# sunclock.net
KiCad netlist of a schematic drawn in EAGLE
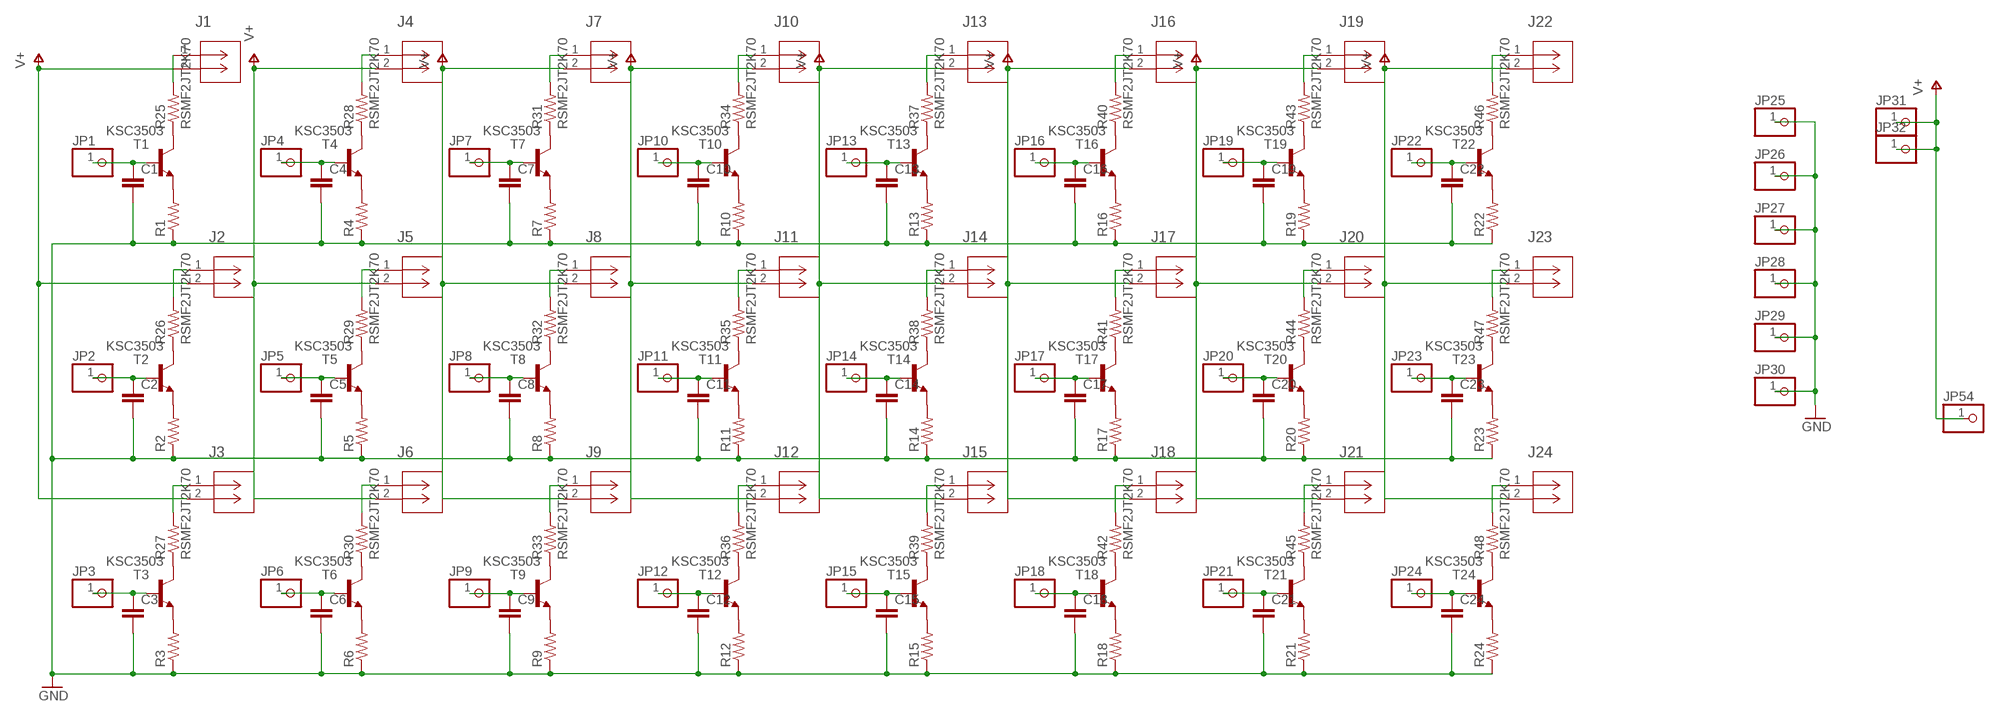
[diagram p0: schematic, sheet 1]

(export (version "E")
  (design (tool "Eeschema 10.0.6"))
  (components
    (comp (ref "C1")
      (value "C-EU050-025X075")
      (footprint "eagle-import:C050-025X075")
      (libsource (lib "eagle-import") (part "C-EU050-025X075"))
    )
    (comp (ref "C2")
      (value "C-EU050-025X075")
      (footprint "eagle-import:C050-025X075")
      (libsource (lib "eagle-import") (part "C-EU050-025X075"))
    )
    (comp (ref "C3")
      (value "C-EU050-025X075")
      (footprint "eagle-import:C050-025X075")
      (libsource (lib "eagle-import") (part "C-EU050-025X075"))
    )
    (comp (ref "C4")
      (value "C-EU050-025X075")
      (footprint "eagle-import:C050-025X075")
      (libsource (lib "eagle-import") (part "C-EU050-025X075"))
    )
    (comp (ref "C5")
      (value "C-EU050-025X075")
      (footprint "eagle-import:C050-025X075")
      (libsource (lib "eagle-import") (part "C-EU050-025X075"))
    )
    (comp (ref "C6")
      (value "C-EU050-025X075")
      (footprint "eagle-import:C050-025X075")
      (libsource (lib "eagle-import") (part "C-EU050-025X075"))
    )
    (comp (ref "C7")
      (value "C-EU050-025X075")
      (footprint "eagle-import:C050-025X075")
      (libsource (lib "eagle-import") (part "C-EU050-025X075"))
    )
    (comp (ref "C8")
      (value "C-EU050-025X075")
      (footprint "eagle-import:C050-025X075")
      (libsource (lib "eagle-import") (part "C-EU050-025X075"))
    )
    (comp (ref "C9")
      (value "C-EU050-025X075")
      (footprint "eagle-import:C050-025X075")
      (libsource (lib "eagle-import") (part "C-EU050-025X075"))
    )
    (comp (ref "C10")
      (value "C-EU050-025X075")
      (footprint "eagle-import:C050-025X075")
      (libsource (lib "eagle-import") (part "C-EU050-025X075"))
    )
    (comp (ref "C11")
      (value "C-EU050-025X075")
      (footprint "eagle-import:C050-025X075")
      (libsource (lib "eagle-import") (part "C-EU050-025X075"))
    )
    (comp (ref "C12")
      (value "C-EU050-025X075")
      (footprint "eagle-import:C050-025X075")
      (libsource (lib "eagle-import") (part "C-EU050-025X075"))
    )
    (comp (ref "C13")
      (value "C-EU050-025X075")
      (footprint "eagle-import:C050-025X075")
      (libsource (lib "eagle-import") (part "C-EU050-025X075"))
    )
    (comp (ref "C14")
      (value "C-EU050-025X075")
      (footprint "eagle-import:C050-025X075")
      (libsource (lib "eagle-import") (part "C-EU050-025X075"))
    )
    (comp (ref "C15")
      (value "C-EU050-025X075")
      (footprint "eagle-import:C050-025X075")
      (libsource (lib "eagle-import") (part "C-EU050-025X075"))
    )
    (comp (ref "C16")
      (value "C-EU050-025X075")
      (footprint "eagle-import:C050-025X075")
      (libsource (lib "eagle-import") (part "C-EU050-025X075"))
    )
    (comp (ref "C17")
      (value "C-EU050-025X075")
      (footprint "eagle-import:C050-025X075")
      (libsource (lib "eagle-import") (part "C-EU050-025X075"))
    )
    (comp (ref "C18")
      (value "C-EU050-025X075")
      (footprint "eagle-import:C050-025X075")
      (libsource (lib "eagle-import") (part "C-EU050-025X075"))
    )
    (comp (ref "C19")
      (value "C-EU050-025X075")
      (footprint "eagle-import:C050-025X075")
      (libsource (lib "eagle-import") (part "C-EU050-025X075"))
    )
    (comp (ref "C20")
      (value "C-EU050-025X075")
      (footprint "eagle-import:C050-025X075")
      (libsource (lib "eagle-import") (part "C-EU050-025X075"))
    )
    (comp (ref "C21")
      (value "C-EU050-025X075")
      (footprint "eagle-import:C050-025X075")
      (libsource (lib "eagle-import") (part "C-EU050-025X075"))
    )
    (comp (ref "C22")
      (value "C-EU050-025X075")
      (footprint "eagle-import:C050-025X075")
      (libsource (lib "eagle-import") (part "C-EU050-025X075"))
    )
    (comp (ref "C23")
      (value "C-EU050-025X075")
      (footprint "eagle-import:C050-025X075")
      (libsource (lib "eagle-import") (part "C-EU050-025X075"))
    )
    (comp (ref "C24")
      (value "C-EU050-025X075")
      (footprint "eagle-import:C050-025X075")
      (libsource (lib "eagle-import") (part "C-EU050-025X075"))
    )
    (comp (ref "J1")
      (value "1776275-2")
      (footprint "eagle-import:CONN2_1776275-2")
      (fields (field (name "COPYRIGHT") "Copyright (C) 2023 Ultra Librarian. All rights reserved."))
      (libsource (lib "eagle-import") (part "1776275-2"))
    )
    (comp (ref "J2")
      (value "1776275-2")
      (footprint "eagle-import:CONN2_1776275-2")
      (fields (field (name "COPYRIGHT") "Copyright (C) 2023 Ultra Librarian. All rights reserved."))
      (libsource (lib "eagle-import") (part "1776275-2"))
    )
    (comp (ref "J3")
      (value "1776275-2")
      (footprint "eagle-import:CONN2_1776275-2")
      (fields (field (name "COPYRIGHT") "Copyright (C) 2023 Ultra Librarian. All rights reserved."))
      (libsource (lib "eagle-import") (part "1776275-2"))
    )
    (comp (ref "J4")
      (value "1776275-2")
      (footprint "eagle-import:CONN2_1776275-2")
      (fields (field (name "COPYRIGHT") "Copyright (C) 2023 Ultra Librarian. All rights reserved."))
      (libsource (lib "eagle-import") (part "1776275-2"))
    )
    (comp (ref "J5")
      (value "1776275-2")
      (footprint "eagle-import:CONN2_1776275-2")
      (fields (field (name "COPYRIGHT") "Copyright (C) 2023 Ultra Librarian. All rights reserved."))
      (libsource (lib "eagle-import") (part "1776275-2"))
    )
    (comp (ref "J6")
      (value "1776275-2")
      (footprint "eagle-import:CONN2_1776275-2")
      (fields (field (name "COPYRIGHT") "Copyright (C) 2023 Ultra Librarian. All rights reserved."))
      (libsource (lib "eagle-import") (part "1776275-2"))
    )
    (comp (ref "J7")
      (value "1776275-2")
      (footprint "eagle-import:CONN2_1776275-2")
      (fields (field (name "COPYRIGHT") "Copyright (C) 2023 Ultra Librarian. All rights reserved."))
      (libsource (lib "eagle-import") (part "1776275-2"))
    )
    (comp (ref "J8")
      (value "1776275-2")
      (footprint "eagle-import:CONN2_1776275-2")
      (fields (field (name "COPYRIGHT") "Copyright (C) 2023 Ultra Librarian. All rights reserved."))
      (libsource (lib "eagle-import") (part "1776275-2"))
    )
    (comp (ref "J9")
      (value "1776275-2")
      (footprint "eagle-import:CONN2_1776275-2")
      (fields (field (name "COPYRIGHT") "Copyright (C) 2023 Ultra Librarian. All rights reserved."))
      (libsource (lib "eagle-import") (part "1776275-2"))
    )
    (comp (ref "J10")
      (value "1776275-2")
      (footprint "eagle-import:CONN2_1776275-2")
      (fields (field (name "COPYRIGHT") "Copyright (C) 2023 Ultra Librarian. All rights reserved."))
      (libsource (lib "eagle-import") (part "1776275-2"))
    )
    (comp (ref "J11")
      (value "1776275-2")
      (footprint "eagle-import:CONN2_1776275-2")
      (fields (field (name "COPYRIGHT") "Copyright (C) 2023 Ultra Librarian. All rights reserved."))
      (libsource (lib "eagle-import") (part "1776275-2"))
    )
    (comp (ref "J12")
      (value "1776275-2")
      (footprint "eagle-import:CONN2_1776275-2")
      (fields (field (name "COPYRIGHT") "Copyright (C) 2023 Ultra Librarian. All rights reserved."))
      (libsource (lib "eagle-import") (part "1776275-2"))
    )
    (comp (ref "J13")
      (value "1776275-2")
      (footprint "eagle-import:CONN2_1776275-2")
      (fields (field (name "COPYRIGHT") "Copyright (C) 2023 Ultra Librarian. All rights reserved."))
      (libsource (lib "eagle-import") (part "1776275-2"))
    )
    (comp (ref "J14")
      (value "1776275-2")
      (footprint "eagle-import:CONN2_1776275-2")
      (fields (field (name "COPYRIGHT") "Copyright (C) 2023 Ultra Librarian. All rights reserved."))
      (libsource (lib "eagle-import") (part "1776275-2"))
    )
    (comp (ref "J15")
      (value "1776275-2")
      (footprint "eagle-import:CONN2_1776275-2")
      (fields (field (name "COPYRIGHT") "Copyright (C) 2023 Ultra Librarian. All rights reserved."))
      (libsource (lib "eagle-import") (part "1776275-2"))
    )
    (comp (ref "J16")
      (value "1776275-2")
      (footprint "eagle-import:CONN2_1776275-2")
      (fields (field (name "COPYRIGHT") "Copyright (C) 2023 Ultra Librarian. All rights reserved."))
      (libsource (lib "eagle-import") (part "1776275-2"))
    )
    (comp (ref "J17")
      (value "1776275-2")
      (footprint "eagle-import:CONN2_1776275-2")
      (fields (field (name "COPYRIGHT") "Copyright (C) 2023 Ultra Librarian. All rights reserved."))
      (libsource (lib "eagle-import") (part "1776275-2"))
    )
    (comp (ref "J18")
      (value "1776275-2")
      (footprint "eagle-import:CONN2_1776275-2")
      (fields (field (name "COPYRIGHT") "Copyright (C) 2023 Ultra Librarian. All rights reserved."))
      (libsource (lib "eagle-import") (part "1776275-2"))
    )
    (comp (ref "J19")
      (value "1776275-2")
      (footprint "eagle-import:CONN2_1776275-2")
      (fields (field (name "COPYRIGHT") "Copyright (C) 2023 Ultra Librarian. All rights reserved."))
      (libsource (lib "eagle-import") (part "1776275-2"))
    )
    (comp (ref "J20")
      (value "1776275-2")
      (footprint "eagle-import:CONN2_1776275-2")
      (fields (field (name "COPYRIGHT") "Copyright (C) 2023 Ultra Librarian. All rights reserved."))
      (libsource (lib "eagle-import") (part "1776275-2"))
    )
    (comp (ref "J21")
      (value "1776275-2")
      (footprint "eagle-import:CONN2_1776275-2")
      (fields (field (name "COPYRIGHT") "Copyright (C) 2023 Ultra Librarian. All rights reserved."))
      (libsource (lib "eagle-import") (part "1776275-2"))
    )
    (comp (ref "J22")
      (value "1776275-2")
      (footprint "eagle-import:CONN2_1776275-2")
      (fields (field (name "COPYRIGHT") "Copyright (C) 2023 Ultra Librarian. All rights reserved."))
      (libsource (lib "eagle-import") (part "1776275-2"))
    )
    (comp (ref "J23")
      (value "1776275-2")
      (footprint "eagle-import:CONN2_1776275-2")
      (fields (field (name "COPYRIGHT") "Copyright (C) 2023 Ultra Librarian. All rights reserved."))
      (libsource (lib "eagle-import") (part "1776275-2"))
    )
    (comp (ref "J24")
      (value "1776275-2")
      (footprint "eagle-import:CONN2_1776275-2")
      (fields (field (name "COPYRIGHT") "Copyright (C) 2023 Ultra Librarian. All rights reserved."))
      (libsource (lib "eagle-import") (part "1776275-2"))
    )
    (comp (ref "JP1")
      (value "PINHD-1X1")
      (footprint "eagle-import:1X01")
      (libsource (lib "eagle-import") (part "PINHD-1X1"))
    )
    (comp (ref "JP2")
      (value "PINHD-1X1")
      (footprint "eagle-import:1X01")
      (libsource (lib "eagle-import") (part "PINHD-1X1"))
    )
    (comp (ref "JP3")
      (value "PINHD-1X1")
      (footprint "eagle-import:1X01")
      (libsource (lib "eagle-import") (part "PINHD-1X1"))
    )
    (comp (ref "JP4")
      (value "PINHD-1X1")
      (footprint "eagle-import:1X01")
      (libsource (lib "eagle-import") (part "PINHD-1X1"))
    )
    (comp (ref "JP5")
      (value "PINHD-1X1")
      (footprint "eagle-import:1X01")
      (libsource (lib "eagle-import") (part "PINHD-1X1"))
    )
    (comp (ref "JP6")
      (value "PINHD-1X1")
      (footprint "eagle-import:1X01")
      (libsource (lib "eagle-import") (part "PINHD-1X1"))
    )
    (comp (ref "JP7")
      (value "PINHD-1X1")
      (footprint "eagle-import:1X01")
      (libsource (lib "eagle-import") (part "PINHD-1X1"))
    )
    (comp (ref "JP8")
      (value "PINHD-1X1")
      (footprint "eagle-import:1X01")
      (libsource (lib "eagle-import") (part "PINHD-1X1"))
    )
    (comp (ref "JP9")
      (value "PINHD-1X1")
      (footprint "eagle-import:1X01")
      (libsource (lib "eagle-import") (part "PINHD-1X1"))
    )
    (comp (ref "JP10")
      (value "PINHD-1X1")
      (footprint "eagle-import:1X01")
      (libsource (lib "eagle-import") (part "PINHD-1X1"))
    )
    (comp (ref "JP11")
      (value "PINHD-1X1")
      (footprint "eagle-import:1X01")
      (libsource (lib "eagle-import") (part "PINHD-1X1"))
    )
    (comp (ref "JP12")
      (value "PINHD-1X1")
      (footprint "eagle-import:1X01")
      (libsource (lib "eagle-import") (part "PINHD-1X1"))
    )
    (comp (ref "JP13")
      (value "PINHD-1X1")
      (footprint "eagle-import:1X01")
      (libsource (lib "eagle-import") (part "PINHD-1X1"))
    )
    (comp (ref "JP14")
      (value "PINHD-1X1")
      (footprint "eagle-import:1X01")
      (libsource (lib "eagle-import") (part "PINHD-1X1"))
    )
    (comp (ref "JP15")
      (value "PINHD-1X1")
      (footprint "eagle-import:1X01")
      (libsource (lib "eagle-import") (part "PINHD-1X1"))
    )
    (comp (ref "JP16")
      (value "PINHD-1X1")
      (footprint "eagle-import:1X01")
      (libsource (lib "eagle-import") (part "PINHD-1X1"))
    )
    (comp (ref "JP17")
      (value "PINHD-1X1")
      (footprint "eagle-import:1X01")
      (libsource (lib "eagle-import") (part "PINHD-1X1"))
    )
    (comp (ref "JP18")
      (value "PINHD-1X1")
      (footprint "eagle-import:1X01")
      (libsource (lib "eagle-import") (part "PINHD-1X1"))
    )
    (comp (ref "JP19")
      (value "PINHD-1X1")
      (footprint "eagle-import:1X01")
      (libsource (lib "eagle-import") (part "PINHD-1X1"))
    )
    (comp (ref "JP20")
      (value "PINHD-1X1")
      (footprint "eagle-import:1X01")
      (libsource (lib "eagle-import") (part "PINHD-1X1"))
    )
    (comp (ref "JP21")
      (value "PINHD-1X1")
      (footprint "eagle-import:1X01")
      (libsource (lib "eagle-import") (part "PINHD-1X1"))
    )
    (comp (ref "JP22")
      (value "PINHD-1X1")
      (footprint "eagle-import:1X01")
      (libsource (lib "eagle-import") (part "PINHD-1X1"))
    )
    (comp (ref "JP23")
      (value "PINHD-1X1")
      (footprint "eagle-import:1X01")
      (libsource (lib "eagle-import") (part "PINHD-1X1"))
    )
    (comp (ref "JP24")
      (value "PINHD-1X1")
      (footprint "eagle-import:1X01")
      (libsource (lib "eagle-import") (part "PINHD-1X1"))
    )
    (comp (ref "JP25")
      (value "PINHD-1X1")
      (footprint "eagle-import:1X01")
      (libsource (lib "eagle-import") (part "PINHD-1X1"))
    )
    (comp (ref "JP26")
      (value "PINHD-1X1")
      (footprint "eagle-import:1X01")
      (libsource (lib "eagle-import") (part "PINHD-1X1"))
    )
    (comp (ref "JP27")
      (value "PINHD-1X1")
      (footprint "eagle-import:1X01")
      (libsource (lib "eagle-import") (part "PINHD-1X1"))
    )
    (comp (ref "JP28")
      (value "PINHD-1X1")
      (footprint "eagle-import:1X01")
      (libsource (lib "eagle-import") (part "PINHD-1X1"))
    )
    (comp (ref "JP29")
      (value "PINHD-1X1")
      (footprint "eagle-import:1X01")
      (libsource (lib "eagle-import") (part "PINHD-1X1"))
    )
    (comp (ref "JP30")
      (value "PINHD-1X1")
      (footprint "eagle-import:1X01")
      (libsource (lib "eagle-import") (part "PINHD-1X1"))
    )
    (comp (ref "JP31")
      (value "PINHD-1X1")
      (footprint "eagle-import:1X01")
      (libsource (lib "eagle-import") (part "PINHD-1X1"))
    )
    (comp (ref "JP32")
      (value "PINHD-1X1")
      (footprint "eagle-import:1X01")
      (libsource (lib "eagle-import") (part "PINHD-1X1"))
    )
    (comp (ref "JP54")
      (value "PINHD-1X1")
      (footprint "eagle-import:1X01")
      (libsource (lib "eagle-import") (part "PINHD-1X1"))
    )
    (comp (ref "R1")
      (value "R-US_0207/10")
      (footprint "eagle-import:0207_10")
      (libsource (lib "eagle-import") (part "R-US_0207/10"))
    )
    (comp (ref "R2")
      (value "R-US_0207/10")
      (footprint "eagle-import:0207_10")
      (libsource (lib "eagle-import") (part "R-US_0207/10"))
    )
    (comp (ref "R3")
      (value "R-US_0207/10")
      (footprint "eagle-import:0207_10")
      (libsource (lib "eagle-import") (part "R-US_0207/10"))
    )
    (comp (ref "R4")
      (value "R-US_0207/10")
      (footprint "eagle-import:0207_10")
      (libsource (lib "eagle-import") (part "R-US_0207/10"))
    )
    (comp (ref "R5")
      (value "R-US_0207/10")
      (footprint "eagle-import:0207_10")
      (libsource (lib "eagle-import") (part "R-US_0207/10"))
    )
    (comp (ref "R6")
      (value "R-US_0207/10")
      (footprint "eagle-import:0207_10")
      (libsource (lib "eagle-import") (part "R-US_0207/10"))
    )
    (comp (ref "R7")
      (value "R-US_0207/10")
      (footprint "eagle-import:0207_10")
      (libsource (lib "eagle-import") (part "R-US_0207/10"))
    )
    (comp (ref "R8")
      (value "R-US_0207/10")
      (footprint "eagle-import:0207_10")
      (libsource (lib "eagle-import") (part "R-US_0207/10"))
    )
    (comp (ref "R9")
      (value "R-US_0207/10")
      (footprint "eagle-import:0207_10")
      (libsource (lib "eagle-import") (part "R-US_0207/10"))
    )
    (comp (ref "R10")
      (value "R-US_0207/10")
      (footprint "eagle-import:0207_10")
      (libsource (lib "eagle-import") (part "R-US_0207/10"))
    )
    (comp (ref "R11")
      (value "R-US_0207/10")
      (footprint "eagle-import:0207_10")
      (libsource (lib "eagle-import") (part "R-US_0207/10"))
    )
    (comp (ref "R12")
      (value "R-US_0207/10")
      (footprint "eagle-import:0207_10")
      (libsource (lib "eagle-import") (part "R-US_0207/10"))
    )
    (comp (ref "R13")
      (value "R-US_0207/10")
      (footprint "eagle-import:0207_10")
      (libsource (lib "eagle-import") (part "R-US_0207/10"))
    )
    (comp (ref "R14")
      (value "R-US_0207/10")
      (footprint "eagle-import:0207_10")
      (libsource (lib "eagle-import") (part "R-US_0207/10"))
    )
    (comp (ref "R15")
      (value "R-US_0207/10")
      (footprint "eagle-import:0207_10")
      (libsource (lib "eagle-import") (part "R-US_0207/10"))
    )
    (comp (ref "R16")
      (value "R-US_0207/10")
      (footprint "eagle-import:0207_10")
      (libsource (lib "eagle-import") (part "R-US_0207/10"))
    )
    (comp (ref "R17")
      (value "R-US_0207/10")
      (footprint "eagle-import:0207_10")
      (libsource (lib "eagle-import") (part "R-US_0207/10"))
    )
    (comp (ref "R18")
      (value "R-US_0207/10")
      (footprint "eagle-import:0207_10")
      (libsource (lib "eagle-import") (part "R-US_0207/10"))
    )
    (comp (ref "R19")
      (value "R-US_0207/10")
      (footprint "eagle-import:0207_10")
      (libsource (lib "eagle-import") (part "R-US_0207/10"))
    )
    (comp (ref "R20")
      (value "R-US_0207/10")
      (footprint "eagle-import:0207_10")
      (libsource (lib "eagle-import") (part "R-US_0207/10"))
    )
    (comp (ref "R21")
      (value "R-US_0207/10")
      (footprint "eagle-import:0207_10")
      (libsource (lib "eagle-import") (part "R-US_0207/10"))
    )
    (comp (ref "R22")
      (value "R-US_0207/10")
      (footprint "eagle-import:0207_10")
      (libsource (lib "eagle-import") (part "R-US_0207/10"))
    )
    (comp (ref "R23")
      (value "R-US_0207/10")
      (footprint "eagle-import:0207_10")
      (libsource (lib "eagle-import") (part "R-US_0207/10"))
    )
    (comp (ref "R24")
      (value "R-US_0207/10")
      (footprint "eagle-import:0207_10")
      (libsource (lib "eagle-import") (part "R-US_0207/10"))
    )
    (comp (ref "R25")
      (value "RSMF2JT2K70")
      (footprint "eagle-import:RESAD1610W80L1100D450B")
      (libsource (lib "eagle-import") (part "RSMF2JT2K70"))
    )
    (comp (ref "R26")
      (value "RSMF2JT2K70")
      (footprint "eagle-import:RESAD1610W80L1100D450B")
      (libsource (lib "eagle-import") (part "RSMF2JT2K70"))
    )
    (comp (ref "R27")
      (value "RSMF2JT2K70")
      (footprint "eagle-import:RESAD1610W80L1100D450B")
      (libsource (lib "eagle-import") (part "RSMF2JT2K70"))
    )
    (comp (ref "R28")
      (value "RSMF2JT2K70")
      (footprint "eagle-import:RESAD1610W80L1100D450B")
      (libsource (lib "eagle-import") (part "RSMF2JT2K70"))
    )
    (comp (ref "R29")
      (value "RSMF2JT2K70")
      (footprint "eagle-import:RESAD1610W80L1100D450B")
      (libsource (lib "eagle-import") (part "RSMF2JT2K70"))
    )
    (comp (ref "R30")
      (value "RSMF2JT2K70")
      (footprint "eagle-import:RESAD1610W80L1100D450B")
      (libsource (lib "eagle-import") (part "RSMF2JT2K70"))
    )
    (comp (ref "R31")
      (value "RSMF2JT2K70")
      (footprint "eagle-import:RESAD1610W80L1100D450B")
      (libsource (lib "eagle-import") (part "RSMF2JT2K70"))
    )
    (comp (ref "R32")
      (value "RSMF2JT2K70")
      (footprint "eagle-import:RESAD1610W80L1100D450B")
      (libsource (lib "eagle-import") (part "RSMF2JT2K70"))
    )
    (comp (ref "R33")
      (value "RSMF2JT2K70")
      (footprint "eagle-import:RESAD1610W80L1100D450B")
      (libsource (lib "eagle-import") (part "RSMF2JT2K70"))
    )
    (comp (ref "R34")
      (value "RSMF2JT2K70")
      (footprint "eagle-import:RESAD1610W80L1100D450B")
      (libsource (lib "eagle-import") (part "RSMF2JT2K70"))
    )
    (comp (ref "R35")
      (value "RSMF2JT2K70")
      (footprint "eagle-import:RESAD1610W80L1100D450B")
      (libsource (lib "eagle-import") (part "RSMF2JT2K70"))
    )
    (comp (ref "R36")
      (value "RSMF2JT2K70")
      (footprint "eagle-import:RESAD1610W80L1100D450B")
      (libsource (lib "eagle-import") (part "RSMF2JT2K70"))
    )
    (comp (ref "R37")
      (value "RSMF2JT2K70")
      (footprint "eagle-import:RESAD1610W80L1100D450B")
      (libsource (lib "eagle-import") (part "RSMF2JT2K70"))
    )
    (comp (ref "R38")
      (value "RSMF2JT2K70")
      (footprint "eagle-import:RESAD1610W80L1100D450B")
      (libsource (lib "eagle-import") (part "RSMF2JT2K70"))
    )
    (comp (ref "R39")
      (value "RSMF2JT2K70")
      (footprint "eagle-import:RESAD1610W80L1100D450B")
      (libsource (lib "eagle-import") (part "RSMF2JT2K70"))
    )
    (comp (ref "R40")
      (value "RSMF2JT2K70")
      (footprint "eagle-import:RESAD1610W80L1100D450B")
      (libsource (lib "eagle-import") (part "RSMF2JT2K70"))
    )
    (comp (ref "R41")
      (value "RSMF2JT2K70")
      (footprint "eagle-import:RESAD1610W80L1100D450B")
      (libsource (lib "eagle-import") (part "RSMF2JT2K70"))
    )
    (comp (ref "R42")
      (value "RSMF2JT2K70")
      (footprint "eagle-import:RESAD1610W80L1100D450B")
      (libsource (lib "eagle-import") (part "RSMF2JT2K70"))
    )
    (comp (ref "R43")
      (value "RSMF2JT2K70")
      (footprint "eagle-import:RESAD1610W80L1100D450B")
      (libsource (lib "eagle-import") (part "RSMF2JT2K70"))
    )
    (comp (ref "R44")
      (value "RSMF2JT2K70")
      (footprint "eagle-import:RESAD1610W80L1100D450B")
      (libsource (lib "eagle-import") (part "RSMF2JT2K70"))
    )
    (comp (ref "R45")
      (value "RSMF2JT2K70")
      (footprint "eagle-import:RESAD1610W80L1100D450B")
      (libsource (lib "eagle-import") (part "RSMF2JT2K70"))
    )
    (comp (ref "R46")
      (value "RSMF2JT2K70")
      (footprint "eagle-import:RESAD1610W80L1100D450B")
      (libsource (lib "eagle-import") (part "RSMF2JT2K70"))
    )
    (comp (ref "R47")
      (value "RSMF2JT2K70")
      (footprint "eagle-import:RESAD1610W80L1100D450B")
      (libsource (lib "eagle-import") (part "RSMF2JT2K70"))
    )
    (comp (ref "R48")
      (value "RSMF2JT2K70")
      (footprint "eagle-import:RESAD1610W80L1100D450B")
      (libsource (lib "eagle-import") (part "RSMF2JT2K70"))
    )
    (comp (ref "T1")
      (value "KSC3503")
      (footprint "eagle-import:TO126V_")
      (libsource (lib "eagle-import") (part "KSC3503"))
    )
    (comp (ref "T2")
      (value "KSC3503")
      (footprint "eagle-import:TO126V_")
      (libsource (lib "eagle-import") (part "KSC3503"))
    )
    (comp (ref "T3")
      (value "KSC3503")
      (footprint "eagle-import:TO126V_")
      (libsource (lib "eagle-import") (part "KSC3503"))
    )
    (comp (ref "T4")
      (value "KSC3503")
      (footprint "eagle-import:TO126V_")
      (libsource (lib "eagle-import") (part "KSC3503"))
    )
    (comp (ref "T5")
      (value "KSC3503")
      (footprint "eagle-import:TO126V_")
      (libsource (lib "eagle-import") (part "KSC3503"))
    )
    (comp (ref "T6")
      (value "KSC3503")
      (footprint "eagle-import:TO126V_")
      (libsource (lib "eagle-import") (part "KSC3503"))
    )
    (comp (ref "T7")
      (value "KSC3503")
      (footprint "eagle-import:TO126V_")
      (libsource (lib "eagle-import") (part "KSC3503"))
    )
    (comp (ref "T8")
      (value "KSC3503")
      (footprint "eagle-import:TO126V_")
      (libsource (lib "eagle-import") (part "KSC3503"))
    )
    (comp (ref "T9")
      (value "KSC3503")
      (footprint "eagle-import:TO126V_")
      (libsource (lib "eagle-import") (part "KSC3503"))
    )
    (comp (ref "T10")
      (value "KSC3503")
      (footprint "eagle-import:TO126V_")
      (libsource (lib "eagle-import") (part "KSC3503"))
    )
    (comp (ref "T11")
      (value "KSC3503")
      (footprint "eagle-import:TO126V_")
      (libsource (lib "eagle-import") (part "KSC3503"))
    )
    (comp (ref "T12")
      (value "KSC3503")
      (footprint "eagle-import:TO126V_")
      (libsource (lib "eagle-import") (part "KSC3503"))
    )
    (comp (ref "T13")
      (value "KSC3503")
      (footprint "eagle-import:TO126V_")
      (libsource (lib "eagle-import") (part "KSC3503"))
    )
    (comp (ref "T14")
      (value "KSC3503")
      (footprint "eagle-import:TO126V_")
      (libsource (lib "eagle-import") (part "KSC3503"))
    )
    (comp (ref "T15")
      (value "KSC3503")
      (footprint "eagle-import:TO126V_")
      (libsource (lib "eagle-import") (part "KSC3503"))
    )
    (comp (ref "T16")
      (value "KSC3503")
      (footprint "eagle-import:TO126V_")
      (libsource (lib "eagle-import") (part "KSC3503"))
    )
    (comp (ref "T17")
      (value "KSC3503")
      (footprint "eagle-import:TO126V_")
      (libsource (lib "eagle-import") (part "KSC3503"))
    )
    (comp (ref "T18")
      (value "KSC3503")
      (footprint "eagle-import:TO126V_")
      (libsource (lib "eagle-import") (part "KSC3503"))
    )
    (comp (ref "T19")
      (value "KSC3503")
      (footprint "eagle-import:TO126V_")
      (libsource (lib "eagle-import") (part "KSC3503"))
    )
    (comp (ref "T20")
      (value "KSC3503")
      (footprint "eagle-import:TO126V_")
      (libsource (lib "eagle-import") (part "KSC3503"))
    )
    (comp (ref "T21")
      (value "KSC3503")
      (footprint "eagle-import:TO126V_")
      (libsource (lib "eagle-import") (part "KSC3503"))
    )
    (comp (ref "T22")
      (value "KSC3503")
      (footprint "eagle-import:TO126V_")
      (libsource (lib "eagle-import") (part "KSC3503"))
    )
    (comp (ref "T23")
      (value "KSC3503")
      (footprint "eagle-import:TO126V_")
      (libsource (lib "eagle-import") (part "KSC3503"))
    )
    (comp (ref "T24")
      (value "KSC3503")
      (footprint "eagle-import:TO126V_")
      (libsource (lib "eagle-import") (part "KSC3503"))
    )
  )
  (nets
    (net (code "1") (name "GND") (class "Default")
      (node (ref "C1") (pin "2") (pinfunction "2_2") (pintype "passive"))
      (node (ref "C10") (pin "2") (pinfunction "2_2") (pintype "passive"))
      (node (ref "C11") (pin "2") (pinfunction "2_2") (pintype "passive"))
      (node (ref "C12") (pin "2") (pinfunction "2_2") (pintype "passive"))
      (node (ref "C13") (pin "2") (pinfunction "2_2") (pintype "passive"))
      (node (ref "C14") (pin "2") (pinfunction "2_2") (pintype "passive"))
      (node (ref "C15") (pin "2") (pinfunction "2_2") (pintype "passive"))
      (node (ref "C16") (pin "2") (pinfunction "2_2") (pintype "passive"))
      (node (ref "C17") (pin "2") (pinfunction "2_2") (pintype "passive"))
      (node (ref "C18") (pin "2") (pinfunction "2_2") (pintype "passive"))
      (node (ref "C19") (pin "2") (pinfunction "2_2") (pintype "passive"))
      (node (ref "C2") (pin "2") (pinfunction "2_2") (pintype "passive"))
      (node (ref "C20") (pin "2") (pinfunction "2_2") (pintype "passive"))
      (node (ref "C21") (pin "2") (pinfunction "2_2") (pintype "passive"))
      (node (ref "C22") (pin "2") (pinfunction "2_2") (pintype "passive"))
      (node (ref "C23") (pin "2") (pinfunction "2_2") (pintype "passive"))
      (node (ref "C24") (pin "2") (pinfunction "2_2") (pintype "passive"))
      (node (ref "C3") (pin "2") (pinfunction "2_2") (pintype "passive"))
      (node (ref "C4") (pin "2") (pinfunction "2_2") (pintype "passive"))
      (node (ref "C5") (pin "2") (pinfunction "2_2") (pintype "passive"))
      (node (ref "C6") (pin "2") (pinfunction "2_2") (pintype "passive"))
      (node (ref "C7") (pin "2") (pinfunction "2_2") (pintype "passive"))
      (node (ref "C8") (pin "2") (pinfunction "2_2") (pintype "passive"))
      (node (ref "C9") (pin "2") (pinfunction "2_2") (pintype "passive"))
      (node (ref "JP25") (pin "1") (pinfunction "1_1") (pintype "passive"))
      (node (ref "JP26") (pin "1") (pinfunction "1_1") (pintype "passive"))
      (node (ref "JP27") (pin "1") (pinfunction "1_1") (pintype "passive"))
      (node (ref "JP28") (pin "1") (pinfunction "1_1") (pintype "passive"))
      (node (ref "JP29") (pin "1") (pinfunction "1_1") (pintype "passive"))
      (node (ref "JP30") (pin "1") (pinfunction "1_1") (pintype "passive"))
      (node (ref "R1") (pin "1") (pinfunction "1_1") (pintype "passive"))
      (node (ref "R10") (pin "1") (pinfunction "1_1") (pintype "passive"))
      (node (ref "R11") (pin "1") (pinfunction "1_1") (pintype "passive"))
      (node (ref "R12") (pin "1") (pinfunction "1_1") (pintype "passive"))
      (node (ref "R13") (pin "1") (pinfunction "1_1") (pintype "passive"))
      (node (ref "R14") (pin "1") (pinfunction "1_1") (pintype "passive"))
      (node (ref "R15") (pin "1") (pinfunction "1_1") (pintype "passive"))
      (node (ref "R16") (pin "1") (pinfunction "1_1") (pintype "passive"))
      (node (ref "R17") (pin "1") (pinfunction "1_1") (pintype "passive"))
      (node (ref "R18") (pin "1") (pinfunction "1_1") (pintype "passive"))
      (node (ref "R19") (pin "1") (pinfunction "1_1") (pintype "passive"))
      (node (ref "R2") (pin "1") (pinfunction "1_1") (pintype "passive"))
      (node (ref "R20") (pin "1") (pinfunction "1_1") (pintype "passive"))
      (node (ref "R21") (pin "1") (pinfunction "1_1") (pintype "passive"))
      (node (ref "R22") (pin "1") (pinfunction "1_1") (pintype "passive"))
      (node (ref "R23") (pin "1") (pinfunction "1_1") (pintype "passive"))
      (node (ref "R24") (pin "1") (pinfunction "1_1") (pintype "passive"))
      (node (ref "R3") (pin "1") (pinfunction "1_1") (pintype "passive"))
      (node (ref "R4") (pin "1") (pinfunction "1_1") (pintype "passive"))
      (node (ref "R5") (pin "1") (pinfunction "1_1") (pintype "passive"))
      (node (ref "R6") (pin "1") (pinfunction "1_1") (pintype "passive"))
      (node (ref "R7") (pin "1") (pinfunction "1_1") (pintype "passive"))
      (node (ref "R8") (pin "1") (pinfunction "1_1") (pintype "passive"))
      (node (ref "R9") (pin "1") (pinfunction "1_1") (pintype "passive"))
    )
    (net (code "2") (name "Net-(J1-Pad1)") (class "Default")
      (node (ref "J1") (pin "1") (pinfunction "1_1") (pintype "passive"))
      (node (ref "R25") (pin "2") (pinfunction "2_2") (pintype "passive"))
    )
    (net (code "3") (name "Net-(J2-Pad1)") (class "Default")
      (node (ref "J2") (pin "1") (pinfunction "1_1") (pintype "passive"))
      (node (ref "R26") (pin "2") (pinfunction "2_2") (pintype "passive"))
    )
    (net (code "4") (name "Net-(J3-Pad1)") (class "Default")
      (node (ref "J3") (pin "1") (pinfunction "1_1") (pintype "passive"))
      (node (ref "R27") (pin "2") (pinfunction "2_2") (pintype "passive"))
    )
    (net (code "5") (name "Net-(J4-Pad1)") (class "Default")
      (node (ref "J4") (pin "1") (pinfunction "1_1") (pintype "passive"))
      (node (ref "R28") (pin "2") (pinfunction "2_2") (pintype "passive"))
    )
    (net (code "6") (name "Net-(J5-Pad1)") (class "Default")
      (node (ref "J5") (pin "1") (pinfunction "1_1") (pintype "passive"))
      (node (ref "R29") (pin "2") (pinfunction "2_2") (pintype "passive"))
    )
    (net (code "7") (name "Net-(J6-Pad1)") (class "Default")
      (node (ref "J6") (pin "1") (pinfunction "1_1") (pintype "passive"))
      (node (ref "R30") (pin "2") (pinfunction "2_2") (pintype "passive"))
    )
    (net (code "8") (name "Net-(J7-Pad1)") (class "Default")
      (node (ref "J7") (pin "1") (pinfunction "1_1") (pintype "passive"))
      (node (ref "R31") (pin "2") (pinfunction "2_2") (pintype "passive"))
    )
    (net (code "9") (name "Net-(J8-Pad1)") (class "Default")
      (node (ref "J8") (pin "1") (pinfunction "1_1") (pintype "passive"))
      (node (ref "R32") (pin "2") (pinfunction "2_2") (pintype "passive"))
    )
    (net (code "10") (name "Net-(J9-Pad1)") (class "Default")
      (node (ref "J9") (pin "1") (pinfunction "1_1") (pintype "passive"))
      (node (ref "R33") (pin "2") (pinfunction "2_2") (pintype "passive"))
    )
    (net (code "11") (name "Net-(J10-Pad1)") (class "Default")
      (node (ref "J10") (pin "1") (pinfunction "1_1") (pintype "passive"))
      (node (ref "R34") (pin "2") (pinfunction "2_2") (pintype "passive"))
    )
    (net (code "12") (name "Net-(J11-Pad1)") (class "Default")
      (node (ref "J11") (pin "1") (pinfunction "1_1") (pintype "passive"))
      (node (ref "R35") (pin "2") (pinfunction "2_2") (pintype "passive"))
    )
    (net (code "13") (name "Net-(J12-Pad1)") (class "Default")
      (node (ref "J12") (pin "1") (pinfunction "1_1") (pintype "passive"))
      (node (ref "R36") (pin "2") (pinfunction "2_2") (pintype "passive"))
    )
    (net (code "14") (name "Net-(J13-Pad1)") (class "Default")
      (node (ref "J13") (pin "1") (pinfunction "1_1") (pintype "passive"))
      (node (ref "R37") (pin "2") (pinfunction "2_2") (pintype "passive"))
    )
    (net (code "15") (name "Net-(J14-Pad1)") (class "Default")
      (node (ref "J14") (pin "1") (pinfunction "1_1") (pintype "passive"))
      (node (ref "R38") (pin "2") (pinfunction "2_2") (pintype "passive"))
    )
    (net (code "16") (name "Net-(J15-Pad1)") (class "Default")
      (node (ref "J15") (pin "1") (pinfunction "1_1") (pintype "passive"))
      (node (ref "R39") (pin "2") (pinfunction "2_2") (pintype "passive"))
    )
    (net (code "17") (name "Net-(J16-Pad1)") (class "Default")
      (node (ref "J16") (pin "1") (pinfunction "1_1") (pintype "passive"))
      (node (ref "R40") (pin "2") (pinfunction "2_2") (pintype "passive"))
    )
    (net (code "18") (name "Net-(J17-Pad1)") (class "Default")
      (node (ref "J17") (pin "1") (pinfunction "1_1") (pintype "passive"))
      (node (ref "R41") (pin "2") (pinfunction "2_2") (pintype "passive"))
    )
    (net (code "19") (name "Net-(J18-Pad1)") (class "Default")
      (node (ref "J18") (pin "1") (pinfunction "1_1") (pintype "passive"))
      (node (ref "R42") (pin "2") (pinfunction "2_2") (pintype "passive"))
    )
    (net (code "20") (name "Net-(J19-Pad1)") (class "Default")
      (node (ref "J19") (pin "1") (pinfunction "1_1") (pintype "passive"))
      (node (ref "R43") (pin "2") (pinfunction "2_2") (pintype "passive"))
    )
    (net (code "21") (name "Net-(J20-Pad1)") (class "Default")
      (node (ref "J20") (pin "1") (pinfunction "1_1") (pintype "passive"))
      (node (ref "R44") (pin "2") (pinfunction "2_2") (pintype "passive"))
    )
    (net (code "22") (name "Net-(J21-Pad1)") (class "Default")
      (node (ref "J21") (pin "1") (pinfunction "1_1") (pintype "passive"))
      (node (ref "R45") (pin "2") (pinfunction "2_2") (pintype "passive"))
    )
    (net (code "23") (name "Net-(J22-Pad1)") (class "Default")
      (node (ref "J22") (pin "1") (pinfunction "1_1") (pintype "passive"))
      (node (ref "R46") (pin "2") (pinfunction "2_2") (pintype "passive"))
    )
    (net (code "24") (name "Net-(J23-Pad1)") (class "Default")
      (node (ref "J23") (pin "1") (pinfunction "1_1") (pintype "passive"))
      (node (ref "R47") (pin "2") (pinfunction "2_2") (pintype "passive"))
    )
    (net (code "25") (name "Net-(J24-Pad1)") (class "Default")
      (node (ref "J24") (pin "1") (pinfunction "1_1") (pintype "passive"))
      (node (ref "R48") (pin "2") (pinfunction "2_2") (pintype "passive"))
    )
    (net (code "26") (name "Net-(T1-B)") (class "Default")
      (node (ref "C1") (pin "1") (pinfunction "1_1") (pintype "passive"))
      (node (ref "JP1") (pin "1") (pinfunction "1_1") (pintype "passive"))
      (node (ref "T1") (pin "3") (pinfunction "B_3") (pintype "passive"))
    )
    (net (code "27") (name "Net-(T1-C)") (class "Default")
      (node (ref "R25") (pin "1") (pinfunction "1_1") (pintype "passive"))
      (node (ref "T1") (pin "2") (pinfunction "C_2") (pintype "passive"))
    )
    (net (code "28") (name "Net-(T1-E)") (class "Default")
      (node (ref "R1") (pin "2") (pinfunction "2_2") (pintype "passive"))
      (node (ref "T1") (pin "1") (pinfunction "E_1") (pintype "passive"))
    )
    (net (code "29") (name "Net-(T2-B)") (class "Default")
      (node (ref "C2") (pin "1") (pinfunction "1_1") (pintype "passive"))
      (node (ref "JP2") (pin "1") (pinfunction "1_1") (pintype "passive"))
      (node (ref "T2") (pin "3") (pinfunction "B_3") (pintype "passive"))
    )
    (net (code "30") (name "Net-(T2-C)") (class "Default")
      (node (ref "R26") (pin "1") (pinfunction "1_1") (pintype "passive"))
      (node (ref "T2") (pin "2") (pinfunction "C_2") (pintype "passive"))
    )
    (net (code "31") (name "Net-(T2-E)") (class "Default")
      (node (ref "R2") (pin "2") (pinfunction "2_2") (pintype "passive"))
      (node (ref "T2") (pin "1") (pinfunction "E_1") (pintype "passive"))
    )
    (net (code "32") (name "Net-(T3-B)") (class "Default")
      (node (ref "C3") (pin "1") (pinfunction "1_1") (pintype "passive"))
      (node (ref "JP3") (pin "1") (pinfunction "1_1") (pintype "passive"))
      (node (ref "T3") (pin "3") (pinfunction "B_3") (pintype "passive"))
    )
    (net (code "33") (name "Net-(T3-C)") (class "Default")
      (node (ref "R27") (pin "1") (pinfunction "1_1") (pintype "passive"))
      (node (ref "T3") (pin "2") (pinfunction "C_2") (pintype "passive"))
    )
    (net (code "34") (name "Net-(T3-E)") (class "Default")
      (node (ref "R3") (pin "2") (pinfunction "2_2") (pintype "passive"))
      (node (ref "T3") (pin "1") (pinfunction "E_1") (pintype "passive"))
    )
    (net (code "35") (name "Net-(T4-B)") (class "Default")
      (node (ref "C4") (pin "1") (pinfunction "1_1") (pintype "passive"))
      (node (ref "JP4") (pin "1") (pinfunction "1_1") (pintype "passive"))
      (node (ref "T4") (pin "3") (pinfunction "B_3") (pintype "passive"))
    )
    (net (code "36") (name "Net-(T4-C)") (class "Default")
      (node (ref "R28") (pin "1") (pinfunction "1_1") (pintype "passive"))
      (node (ref "T4") (pin "2") (pinfunction "C_2") (pintype "passive"))
    )
    (net (code "37") (name "Net-(T4-E)") (class "Default")
      (node (ref "R4") (pin "2") (pinfunction "2_2") (pintype "passive"))
      (node (ref "T4") (pin "1") (pinfunction "E_1") (pintype "passive"))
    )
    (net (code "38") (name "Net-(T5-B)") (class "Default")
      (node (ref "C5") (pin "1") (pinfunction "1_1") (pintype "passive"))
      (node (ref "JP5") (pin "1") (pinfunction "1_1") (pintype "passive"))
      (node (ref "T5") (pin "3") (pinfunction "B_3") (pintype "passive"))
    )
    (net (code "39") (name "Net-(T5-C)") (class "Default")
      (node (ref "R29") (pin "1") (pinfunction "1_1") (pintype "passive"))
      (node (ref "T5") (pin "2") (pinfunction "C_2") (pintype "passive"))
    )
    (net (code "40") (name "Net-(T5-E)") (class "Default")
      (node (ref "R5") (pin "2") (pinfunction "2_2") (pintype "passive"))
      (node (ref "T5") (pin "1") (pinfunction "E_1") (pintype "passive"))
    )
    (net (code "41") (name "Net-(T6-B)") (class "Default")
      (node (ref "C6") (pin "1") (pinfunction "1_1") (pintype "passive"))
      (node (ref "JP6") (pin "1") (pinfunction "1_1") (pintype "passive"))
      (node (ref "T6") (pin "3") (pinfunction "B_3") (pintype "passive"))
    )
    (net (code "42") (name "Net-(T6-C)") (class "Default")
      (node (ref "R30") (pin "1") (pinfunction "1_1") (pintype "passive"))
      (node (ref "T6") (pin "2") (pinfunction "C_2") (pintype "passive"))
    )
    (net (code "43") (name "Net-(T6-E)") (class "Default")
      (node (ref "R6") (pin "2") (pinfunction "2_2") (pintype "passive"))
      (node (ref "T6") (pin "1") (pinfunction "E_1") (pintype "passive"))
    )
    (net (code "44") (name "Net-(T7-B)") (class "Default")
      (node (ref "C7") (pin "1") (pinfunction "1_1") (pintype "passive"))
      (node (ref "JP7") (pin "1") (pinfunction "1_1") (pintype "passive"))
      (node (ref "T7") (pin "3") (pinfunction "B_3") (pintype "passive"))
    )
    (net (code "45") (name "Net-(T7-C)") (class "Default")
      (node (ref "R31") (pin "1") (pinfunction "1_1") (pintype "passive"))
      (node (ref "T7") (pin "2") (pinfunction "C_2") (pintype "passive"))
    )
    (net (code "46") (name "Net-(T7-E)") (class "Default")
      (node (ref "R7") (pin "2") (pinfunction "2_2") (pintype "passive"))
      (node (ref "T7") (pin "1") (pinfunction "E_1") (pintype "passive"))
    )
    (net (code "47") (name "Net-(T8-B)") (class "Default")
      (node (ref "C8") (pin "1") (pinfunction "1_1") (pintype "passive"))
      (node (ref "JP8") (pin "1") (pinfunction "1_1") (pintype "passive"))
      (node (ref "T8") (pin "3") (pinfunction "B_3") (pintype "passive"))
    )
    (net (code "48") (name "Net-(T8-C)") (class "Default")
      (node (ref "R32") (pin "1") (pinfunction "1_1") (pintype "passive"))
      (node (ref "T8") (pin "2") (pinfunction "C_2") (pintype "passive"))
    )
    (net (code "49") (name "Net-(T8-E)") (class "Default")
      (node (ref "R8") (pin "2") (pinfunction "2_2") (pintype "passive"))
      (node (ref "T8") (pin "1") (pinfunction "E_1") (pintype "passive"))
    )
    (net (code "50") (name "Net-(T9-B)") (class "Default")
      (node (ref "C9") (pin "1") (pinfunction "1_1") (pintype "passive"))
      (node (ref "JP9") (pin "1") (pinfunction "1_1") (pintype "passive"))
      (node (ref "T9") (pin "3") (pinfunction "B_3") (pintype "passive"))
    )
    (net (code "51") (name "Net-(T9-C)") (class "Default")
      (node (ref "R33") (pin "1") (pinfunction "1_1") (pintype "passive"))
      (node (ref "T9") (pin "2") (pinfunction "C_2") (pintype "passive"))
    )
    (net (code "52") (name "Net-(T9-E)") (class "Default")
      (node (ref "R9") (pin "2") (pinfunction "2_2") (pintype "passive"))
      (node (ref "T9") (pin "1") (pinfunction "E_1") (pintype "passive"))
    )
    (net (code "53") (name "Net-(T10-B)") (class "Default")
      (node (ref "C10") (pin "1") (pinfunction "1_1") (pintype "passive"))
      (node (ref "JP10") (pin "1") (pinfunction "1_1") (pintype "passive"))
      (node (ref "T10") (pin "3") (pinfunction "B_3") (pintype "passive"))
    )
    (net (code "54") (name "Net-(T10-C)") (class "Default")
      (node (ref "R34") (pin "1") (pinfunction "1_1") (pintype "passive"))
      (node (ref "T10") (pin "2") (pinfunction "C_2") (pintype "passive"))
    )
    (net (code "55") (name "Net-(T10-E)") (class "Default")
      (node (ref "R10") (pin "2") (pinfunction "2_2") (pintype "passive"))
      (node (ref "T10") (pin "1") (pinfunction "E_1") (pintype "passive"))
    )
    (net (code "56") (name "Net-(T11-B)") (class "Default")
      (node (ref "C11") (pin "1") (pinfunction "1_1") (pintype "passive"))
      (node (ref "JP11") (pin "1") (pinfunction "1_1") (pintype "passive"))
      (node (ref "T11") (pin "3") (pinfunction "B_3") (pintype "passive"))
    )
    (net (code "57") (name "Net-(T11-C)") (class "Default")
      (node (ref "R35") (pin "1") (pinfunction "1_1") (pintype "passive"))
      (node (ref "T11") (pin "2") (pinfunction "C_2") (pintype "passive"))
    )
    (net (code "58") (name "Net-(T11-E)") (class "Default")
      (node (ref "R11") (pin "2") (pinfunction "2_2") (pintype "passive"))
      (node (ref "T11") (pin "1") (pinfunction "E_1") (pintype "passive"))
    )
    (net (code "59") (name "Net-(T12-B)") (class "Default")
      (node (ref "C12") (pin "1") (pinfunction "1_1") (pintype "passive"))
      (node (ref "JP12") (pin "1") (pinfunction "1_1") (pintype "passive"))
      (node (ref "T12") (pin "3") (pinfunction "B_3") (pintype "passive"))
    )
    (net (code "60") (name "Net-(T12-C)") (class "Default")
      (node (ref "R36") (pin "1") (pinfunction "1_1") (pintype "passive"))
      (node (ref "T12") (pin "2") (pinfunction "C_2") (pintype "passive"))
    )
    (net (code "61") (name "Net-(T12-E)") (class "Default")
      (node (ref "R12") (pin "2") (pinfunction "2_2") (pintype "passive"))
      (node (ref "T12") (pin "1") (pinfunction "E_1") (pintype "passive"))
    )
    (net (code "62") (name "Net-(T13-B)") (class "Default")
      (node (ref "C13") (pin "1") (pinfunction "1_1") (pintype "passive"))
      (node (ref "JP13") (pin "1") (pinfunction "1_1") (pintype "passive"))
      (node (ref "T13") (pin "3") (pinfunction "B_3") (pintype "passive"))
    )
    (net (code "63") (name "Net-(T13-C)") (class "Default")
      (node (ref "R37") (pin "1") (pinfunction "1_1") (pintype "passive"))
      (node (ref "T13") (pin "2") (pinfunction "C_2") (pintype "passive"))
    )
    (net (code "64") (name "Net-(T13-E)") (class "Default")
      (node (ref "R13") (pin "2") (pinfunction "2_2") (pintype "passive"))
      (node (ref "T13") (pin "1") (pinfunction "E_1") (pintype "passive"))
    )
    (net (code "65") (name "Net-(T14-B)") (class "Default")
      (node (ref "C14") (pin "1") (pinfunction "1_1") (pintype "passive"))
      (node (ref "JP14") (pin "1") (pinfunction "1_1") (pintype "passive"))
      (node (ref "T14") (pin "3") (pinfunction "B_3") (pintype "passive"))
    )
    (net (code "66") (name "Net-(T14-C)") (class "Default")
      (node (ref "R38") (pin "1") (pinfunction "1_1") (pintype "passive"))
      (node (ref "T14") (pin "2") (pinfunction "C_2") (pintype "passive"))
    )
    (net (code "67") (name "Net-(T14-E)") (class "Default")
      (node (ref "R14") (pin "2") (pinfunction "2_2") (pintype "passive"))
      (node (ref "T14") (pin "1") (pinfunction "E_1") (pintype "passive"))
    )
    (net (code "68") (name "Net-(T15-B)") (class "Default")
      (node (ref "C15") (pin "1") (pinfunction "1_1") (pintype "passive"))
      (node (ref "JP15") (pin "1") (pinfunction "1_1") (pintype "passive"))
      (node (ref "T15") (pin "3") (pinfunction "B_3") (pintype "passive"))
    )
    (net (code "69") (name "Net-(T15-C)") (class "Default")
      (node (ref "R39") (pin "1") (pinfunction "1_1") (pintype "passive"))
      (node (ref "T15") (pin "2") (pinfunction "C_2") (pintype "passive"))
    )
    (net (code "70") (name "Net-(T15-E)") (class "Default")
      (node (ref "R15") (pin "2") (pinfunction "2_2") (pintype "passive"))
      (node (ref "T15") (pin "1") (pinfunction "E_1") (pintype "passive"))
    )
    (net (code "71") (name "Net-(T16-B)") (class "Default")
      (node (ref "C16") (pin "1") (pinfunction "1_1") (pintype "passive"))
      (node (ref "JP16") (pin "1") (pinfunction "1_1") (pintype "passive"))
      (node (ref "T16") (pin "3") (pinfunction "B_3") (pintype "passive"))
    )
    (net (code "72") (name "Net-(T16-C)") (class "Default")
      (node (ref "R40") (pin "1") (pinfunction "1_1") (pintype "passive"))
      (node (ref "T16") (pin "2") (pinfunction "C_2") (pintype "passive"))
    )
    (net (code "73") (name "Net-(T16-E)") (class "Default")
      (node (ref "R16") (pin "2") (pinfunction "2_2") (pintype "passive"))
      (node (ref "T16") (pin "1") (pinfunction "E_1") (pintype "passive"))
    )
    (net (code "74") (name "Net-(T17-B)") (class "Default")
      (node (ref "C17") (pin "1") (pinfunction "1_1") (pintype "passive"))
      (node (ref "JP17") (pin "1") (pinfunction "1_1") (pintype "passive"))
      (node (ref "T17") (pin "3") (pinfunction "B_3") (pintype "passive"))
    )
    (net (code "75") (name "Net-(T17-C)") (class "Default")
      (node (ref "R41") (pin "1") (pinfunction "1_1") (pintype "passive"))
      (node (ref "T17") (pin "2") (pinfunction "C_2") (pintype "passive"))
    )
    (net (code "76") (name "Net-(T17-E)") (class "Default")
      (node (ref "R17") (pin "2") (pinfunction "2_2") (pintype "passive"))
      (node (ref "T17") (pin "1") (pinfunction "E_1") (pintype "passive"))
    )
    (net (code "77") (name "Net-(T18-B)") (class "Default")
      (node (ref "C18") (pin "1") (pinfunction "1_1") (pintype "passive"))
      (node (ref "JP18") (pin "1") (pinfunction "1_1") (pintype "passive"))
      (node (ref "T18") (pin "3") (pinfunction "B_3") (pintype "passive"))
    )
    (net (code "78") (name "Net-(T18-C)") (class "Default")
      (node (ref "R42") (pin "1") (pinfunction "1_1") (pintype "passive"))
      (node (ref "T18") (pin "2") (pinfunction "C_2") (pintype "passive"))
    )
    (net (code "79") (name "Net-(T18-E)") (class "Default")
      (node (ref "R18") (pin "2") (pinfunction "2_2") (pintype "passive"))
      (node (ref "T18") (pin "1") (pinfunction "E_1") (pintype "passive"))
    )
    (net (code "80") (name "Net-(T19-B)") (class "Default")
      (node (ref "C19") (pin "1") (pinfunction "1_1") (pintype "passive"))
      (node (ref "JP19") (pin "1") (pinfunction "1_1") (pintype "passive"))
      (node (ref "T19") (pin "3") (pinfunction "B_3") (pintype "passive"))
    )
    (net (code "81") (name "Net-(T19-C)") (class "Default")
      (node (ref "R43") (pin "1") (pinfunction "1_1") (pintype "passive"))
      (node (ref "T19") (pin "2") (pinfunction "C_2") (pintype "passive"))
    )
    (net (code "82") (name "Net-(T19-E)") (class "Default")
      (node (ref "R19") (pin "2") (pinfunction "2_2") (pintype "passive"))
      (node (ref "T19") (pin "1") (pinfunction "E_1") (pintype "passive"))
    )
    (net (code "83") (name "Net-(T20-B)") (class "Default")
      (node (ref "C20") (pin "1") (pinfunction "1_1") (pintype "passive"))
      (node (ref "JP20") (pin "1") (pinfunction "1_1") (pintype "passive"))
      (node (ref "T20") (pin "3") (pinfunction "B_3") (pintype "passive"))
    )
    (net (code "84") (name "Net-(T20-C)") (class "Default")
      (node (ref "R44") (pin "1") (pinfunction "1_1") (pintype "passive"))
      (node (ref "T20") (pin "2") (pinfunction "C_2") (pintype "passive"))
    )
    (net (code "85") (name "Net-(T20-E)") (class "Default")
      (node (ref "R20") (pin "2") (pinfunction "2_2") (pintype "passive"))
      (node (ref "T20") (pin "1") (pinfunction "E_1") (pintype "passive"))
    )
    (net (code "86") (name "Net-(T21-B)") (class "Default")
      (node (ref "C21") (pin "1") (pinfunction "1_1") (pintype "passive"))
      (node (ref "JP21") (pin "1") (pinfunction "1_1") (pintype "passive"))
      (node (ref "T21") (pin "3") (pinfunction "B_3") (pintype "passive"))
    )
    (net (code "87") (name "Net-(T21-C)") (class "Default")
      (node (ref "R45") (pin "1") (pinfunction "1_1") (pintype "passive"))
      (node (ref "T21") (pin "2") (pinfunction "C_2") (pintype "passive"))
    )
    (net (code "88") (name "Net-(T21-E)") (class "Default")
      (node (ref "R21") (pin "2") (pinfunction "2_2") (pintype "passive"))
      (node (ref "T21") (pin "1") (pinfunction "E_1") (pintype "passive"))
    )
    (net (code "89") (name "Net-(T22-B)") (class "Default")
      (node (ref "C22") (pin "1") (pinfunction "1_1") (pintype "passive"))
      (node (ref "JP22") (pin "1") (pinfunction "1_1") (pintype "passive"))
      (node (ref "T22") (pin "3") (pinfunction "B_3") (pintype "passive"))
    )
    (net (code "90") (name "Net-(T22-C)") (class "Default")
      (node (ref "R46") (pin "1") (pinfunction "1_1") (pintype "passive"))
      (node (ref "T22") (pin "2") (pinfunction "C_2") (pintype "passive"))
    )
    (net (code "91") (name "Net-(T22-E)") (class "Default")
      (node (ref "R22") (pin "2") (pinfunction "2_2") (pintype "passive"))
      (node (ref "T22") (pin "1") (pinfunction "E_1") (pintype "passive"))
    )
    (net (code "92") (name "Net-(T23-B)") (class "Default")
      (node (ref "C23") (pin "1") (pinfunction "1_1") (pintype "passive"))
      (node (ref "JP23") (pin "1") (pinfunction "1_1") (pintype "passive"))
      (node (ref "T23") (pin "3") (pinfunction "B_3") (pintype "passive"))
    )
    (net (code "93") (name "Net-(T23-C)") (class "Default")
      (node (ref "R47") (pin "1") (pinfunction "1_1") (pintype "passive"))
      (node (ref "T23") (pin "2") (pinfunction "C_2") (pintype "passive"))
    )
    (net (code "94") (name "Net-(T23-E)") (class "Default")
      (node (ref "R23") (pin "2") (pinfunction "2_2") (pintype "passive"))
      (node (ref "T23") (pin "1") (pinfunction "E_1") (pintype "passive"))
    )
    (net (code "95") (name "Net-(T24-B)") (class "Default")
      (node (ref "C24") (pin "1") (pinfunction "1_1") (pintype "passive"))
      (node (ref "JP24") (pin "1") (pinfunction "1_1") (pintype "passive"))
      (node (ref "T24") (pin "3") (pinfunction "B_3") (pintype "passive"))
    )
    (net (code "96") (name "Net-(T24-C)") (class "Default")
      (node (ref "R48") (pin "1") (pinfunction "1_1") (pintype "passive"))
      (node (ref "T24") (pin "2") (pinfunction "C_2") (pintype "passive"))
    )
    (net (code "97") (name "Net-(T24-E)") (class "Default")
      (node (ref "R24") (pin "2") (pinfunction "2_2") (pintype "passive"))
      (node (ref "T24") (pin "1") (pinfunction "E_1") (pintype "passive"))
    )
    (net (code "98") (name "V+") (class "Default")
      (node (ref "J1") (pin "2") (pinfunction "2_2") (pintype "passive"))
      (node (ref "J10") (pin "2") (pinfunction "2_2") (pintype "passive"))
      (node (ref "J11") (pin "2") (pinfunction "2_2") (pintype "passive"))
      (node (ref "J12") (pin "2") (pinfunction "2_2") (pintype "passive"))
      (node (ref "J13") (pin "2") (pinfunction "2_2") (pintype "passive"))
      (node (ref "J14") (pin "2") (pinfunction "2_2") (pintype "passive"))
      (node (ref "J15") (pin "2") (pinfunction "2_2") (pintype "passive"))
      (node (ref "J16") (pin "2") (pinfunction "2_2") (pintype "passive"))
      (node (ref "J17") (pin "2") (pinfunction "2_2") (pintype "passive"))
      (node (ref "J18") (pin "2") (pinfunction "2_2") (pintype "passive"))
      (node (ref "J19") (pin "2") (pinfunction "2_2") (pintype "passive"))
      (node (ref "J2") (pin "2") (pinfunction "2_2") (pintype "passive"))
      (node (ref "J20") (pin "2") (pinfunction "2_2") (pintype "passive"))
      (node (ref "J21") (pin "2") (pinfunction "2_2") (pintype "passive"))
      (node (ref "J22") (pin "2") (pinfunction "2_2") (pintype "passive"))
      (node (ref "J23") (pin "2") (pinfunction "2_2") (pintype "passive"))
      (node (ref "J24") (pin "2") (pinfunction "2_2") (pintype "passive"))
      (node (ref "J3") (pin "2") (pinfunction "2_2") (pintype "passive"))
      (node (ref "J4") (pin "2") (pinfunction "2_2") (pintype "passive"))
      (node (ref "J5") (pin "2") (pinfunction "2_2") (pintype "passive"))
      (node (ref "J6") (pin "2") (pinfunction "2_2") (pintype "passive"))
      (node (ref "J7") (pin "2") (pinfunction "2_2") (pintype "passive"))
      (node (ref "J8") (pin "2") (pinfunction "2_2") (pintype "passive"))
      (node (ref "J9") (pin "2") (pinfunction "2_2") (pintype "passive"))
      (node (ref "JP31") (pin "1") (pinfunction "1_1") (pintype "passive"))
      (node (ref "JP32") (pin "1") (pinfunction "1_1") (pintype "passive"))
      (node (ref "JP54") (pin "1") (pinfunction "1_1") (pintype "passive"))
    )
  )
)
